# CPU.net
KiCad netlist of a schematic drawn in Altium Designer
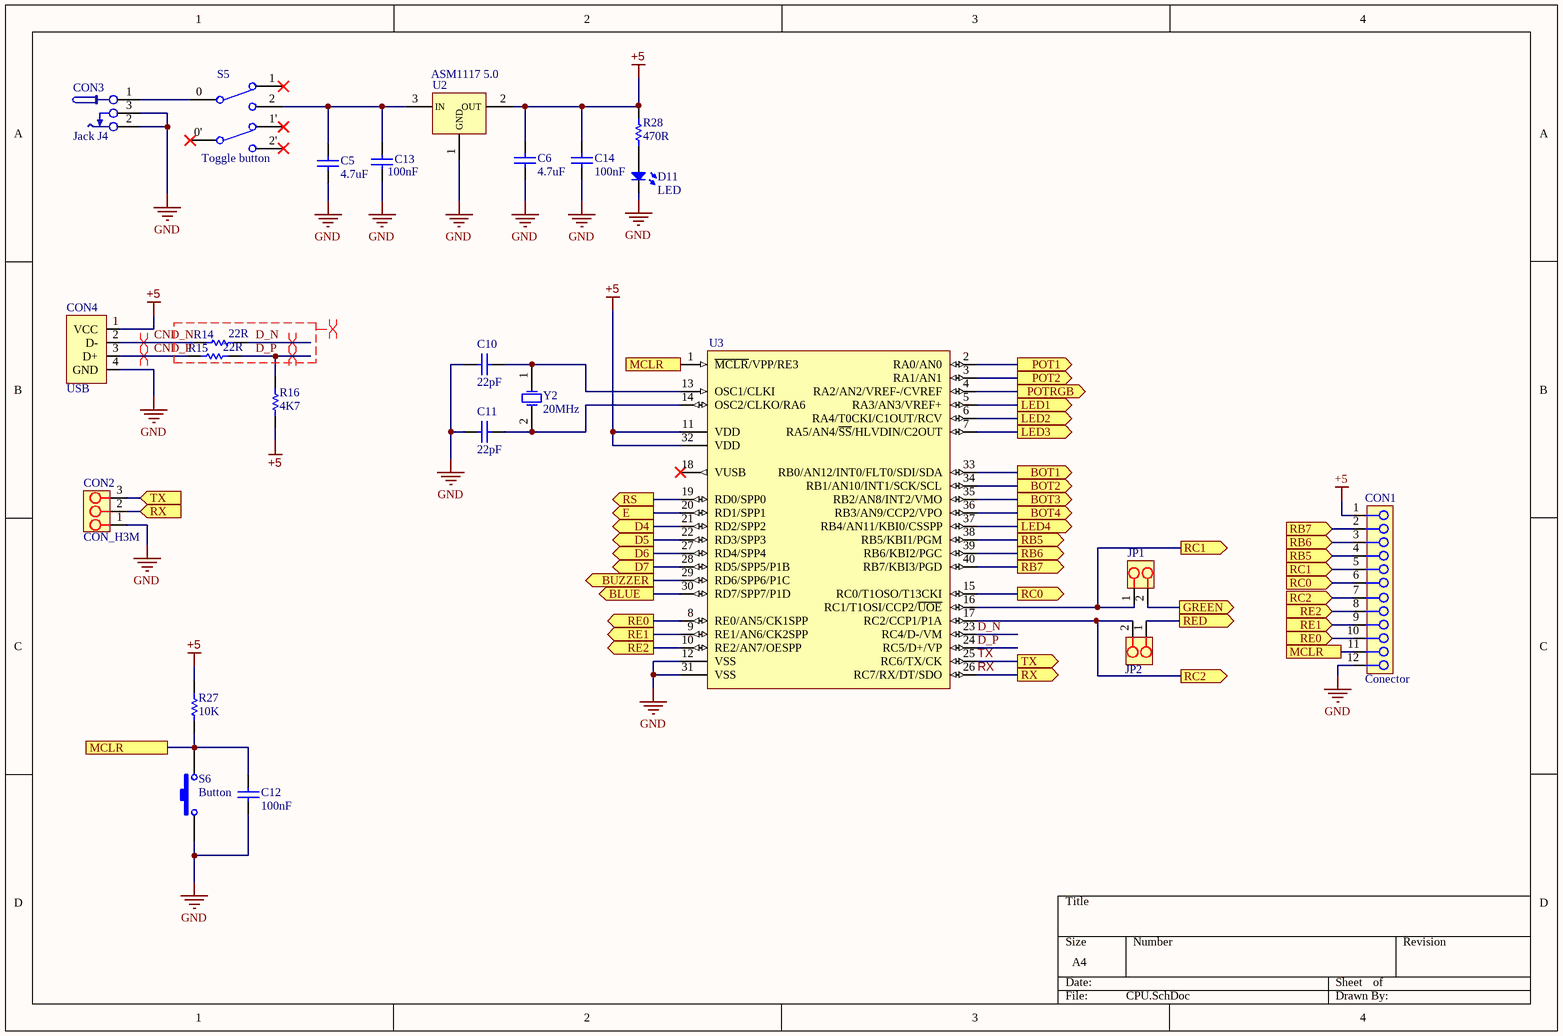
[diagram p0: CPU.SchDoc]

(export (version "E")
  (design (tool "Eeschema 10.0.6"))
  (components
    (comp (ref "C5")
      (value "4.7uF")
      (footprint "CAP_ELEC_1206")
      (description "Capacitor Cerâmico SMD X7R 50V - 1206")
      (libsource (lib "HEIMDALL-DEVPICKIT-V2.1") (part "SMD Eletrolitic Capacitor"))
    )
    (comp (ref "C6")
      (value "4.7uF")
      (footprint "CAP_ELEC_1206")
      (description "Capacitor Cerâmico SMD X7R 50V - 1206")
      (libsource (lib "HEIMDALL-DEVPICKIT-V2.1") (part "SMD Eletrolitic Capacitor"))
    )
    (comp (ref "C10")
      (value "22pF")
      (footprint "SMD Capacitor")
      (description "Multilayer Ceramic\r\nCapacitor 0805")
      (libsource (lib "Aken") (part "SMD Capacitor"))
    )
    (comp (ref "C11")
      (value "22pF")
      (footprint "SMD Capacitor")
      (description "Multilayer Ceramic\r\nCapacitor 0805")
      (libsource (lib "Aken") (part "SMD Capacitor"))
    )
    (comp (ref "C12")
      (value "100nF")
      (footprint "SMD Capacitor")
      (description "Multilayer Ceramic\r\nCapacitor 0805")
      (libsource (lib "Aken") (part "SMD Capacitor"))
    )
    (comp (ref "C13")
      (value "100nF")
      (footprint "SMD Capacitor")
      (description "Multilayer Ceramic\r\nCapacitor 0805")
      (libsource (lib "Aken") (part "SMD Capacitor"))
    )
    (comp (ref "C14")
      (value "100nF")
      (footprint "SMD Capacitor")
      (description "Multilayer Ceramic\r\nCapacitor 0805")
      (libsource (lib "Aken") (part "SMD Capacitor"))
    )
    (comp (ref "CON1") (value "Conector") (footprint "CON_6x2_M") (libsource (lib "Aken") (part "CON_6x2_M")))
    (comp (ref "CON2")
      (value "CON_H3M")
      (footprint "CON_3P_M")
      (description "Molex M 3T")
      (libsource (lib "Aken") (part "CON_H3M"))
    )
    (comp (ref "CON3")
      (value "Jack J4")
      (footprint "J4")
      (description "Conector DC Power Jack J4 2.5mm")
      (fields (field (name "MANUFACTURER") "CUI") (field (name "MANUFACTURER PART NUMBER") "PJ-102BH"))
      (libsource (lib "Adono_Library2") (part "CON-J4"))
    )
    (comp (ref "CON4")
      (value "USB")
      (footprint "USB_SMD")
      (description "Porta USB \r\ntipo B femea")
      (libsource (lib "HEIMDALL-DEVPICKIT-V2.1") (part "Porta_USB_B"))
    )
    (comp (ref "D11")
      (value "LED")
      (footprint "LED_GREEN")
      (description "Light Emissor Diode - 5mm")
      (fields
        (field (name "MANUFACTURER") "Kingbright")
        (field (name "MANUFACTURER PART NUMBER") "WP7113LGD")
      )
      (libsource (lib "Adono_Library2") (part "LED-GREEN"))
    )
    (comp (ref "JP1")
      (value "CON_H2M")
      (footprint "Header2-M")
      (description "Molex M 2T")
      (fields (field (name "MANUFACTURER") "Harwin") (field (name "MANUFACTURER PART NUMBER") "M20-9990246"))
      (libsource (lib "") (part "CON_H2M_1"))
    )
    (comp (ref "JP2")
      (value "CON_H2M")
      (footprint "Header2-M")
      (description "Molex M 2T")
      (fields (field (name "MANUFACTURER") "Harwin") (field (name "MANUFACTURER PART NUMBER") "M20-9990246"))
      (libsource (lib "Adono_Library") (part "CON_H2M"))
    )
    (comp (ref "R14")
      (value "22R")
      (footprint "SMD Resistor")
      (description "SMD Resistor  MCU 0805")
      (libsource (lib "HEIMDALL-DEVPICKIT-V2.1") (part "SMD Resistor"))
    )
    (comp (ref "R15")
      (value "22R")
      (footprint "SMD Resistor")
      (description "SMD Resistor  MCU 0805")
      (libsource (lib "HEIMDALL-DEVPICKIT-V2.1") (part "SMD Resistor"))
    )
    (comp (ref "R16")
      (value "4K7")
      (footprint "SMD Resistor")
      (description "SMD Resistor  MCU 0805")
      (libsource (lib "HEIMDALL-DEVPICKIT-V2.1") (part "SMD Resistor"))
    )
    (comp (ref "R27")
      (value "10K")
      (footprint "SMD Resistor")
      (description "SMD Resistor  MCU 0805")
      (libsource (lib "Aken") (part "SMD Resistor"))
    )
    (comp (ref "R28")
      (value "470R")
      (footprint "SMD Resistor")
      (description "SMD Resistor  MCU 0805")
      (libsource (lib "Aken") (part "SMD Resistor"))
    )
    (comp (ref "S5")
      (value "Toggle button")
      (footprint "Toggle button")
      (libsource (lib "Aken") (part "Toggle button"))
    )
    (comp (ref "S6")
      (value "Button")
      (footprint "BUTTON")
      (description "Tactil Switch")
      (fields
        (field (name "MANUFACTURER") "Panasonic")
        (field (name "MANUFACTURER PART NUMBER") "EVQ-PAC07K")
      )
      (libsource (lib "Adono_Library2") (part "Button"))
    )
    (comp (ref "U2")
      (value "ASM1117 5.0")
      (footprint "ASM1117 5.0")
      (description "LOW DROPOUT VOLTAGE REGULATOR")
      (libsource (lib "Aken") (part "ASM1117 5.0"))
    )
    (comp (ref "U3")
      (value "PIC18F4550")
      (footprint "DIP40")
      (fields
        (field (name "MANUFACTURER") "Microchip")
        (field (name "MANUFACTURER PART NUMBER") "PIC18F4550-I/P")
      )
      (libsource (lib "Adono_Library2") (part "PIC18F4550"))
    )
    (comp (ref "Y2")
      (value "20MHz")
      (footprint "CRYSTAL")
      (description "Quartz Crystal")
      (fields
        (field (name "MANUFACTURER") "ECS International")
        (field (name "MANUFACTURER PART NUMBER") "ECS-200-18-4XEN")
      )
      (libsource (lib "Adono_Library") (part "Crystal_Oscillator"))
    )
  )
  (nets
    (net (code "1") (name "+5") (class "Default")
      (node (ref "C14") (pin "2") (pinfunction "2_2") (pintype "passive"))
      (node (ref "C6") (pin "2") (pinfunction "2_2") (pintype "passive"))
      (node (ref "CON1") (pin "1") (pinfunction "1_1") (pintype "passive"))
      (node (ref "CON4") (pin "1") (pinfunction "VCC_1") (pintype "passive"))
      (node (ref "R16") (pin "1") (pinfunction "1_1") (pintype "passive"))
      (node (ref "R27") (pin "2") (pinfunction "2_2") (pintype "passive"))
      (node (ref "R28") (pin "2") (pinfunction "2_2") (pintype "passive"))
      (node (ref "U2") (pin "2") (pinfunction "OUT_2") (pintype "passive"))
      (node (ref "U3") (pin "11") (pinfunction "VDD_11") (pintype "power_in"))
      (node (ref "U3") (pin "32") (pinfunction "VDD_32") (pintype "power_in"))
    )
    (net (code "2") (name "/BLUE") (class "Default")
      (node (ref "U3") (pin "30") (pinfunction "RD7/SPP7/P1D_30") (pintype "bidirectional"))
    )
    (net (code "3") (name "/BOT1") (class "Default")
      (node (ref "U3") (pin "33") (pinfunction "RB0/AN12/INT0/FLT0/SDI/SDA_33") (pintype "bidirectional"))
    )
    (net (code "4") (name "/BOT2") (class "Default")
      (node (ref "U3") (pin "34") (pinfunction "RB1/AN10/INT1/SCK/SCL_34") (pintype "bidirectional"))
    )
    (net (code "5") (name "/BOT3") (class "Default")
      (node (ref "U3") (pin "35") (pinfunction "RB2/AN8/INT2/VMO_35") (pintype "bidirectional"))
    )
    (net (code "6") (name "/BOT4") (class "Default")
      (node (ref "U3") (pin "36") (pinfunction "RB3/AN9/CCP2/VPO_36") (pintype "bidirectional"))
    )
    (net (code "7") (name "/BUZZER") (class "Default")
      (node (ref "U3") (pin "29") (pinfunction "RD6/SPP6/P1C_29") (pintype "bidirectional"))
    )
    (net (code "8") (name "/CND_N") (class "Default")
      (node (ref "CON4") (pin "2") (pinfunction "D-_2") (pintype "passive"))
      (node (ref "R14") (pin "1") (pinfunction "1_1") (pintype "passive"))
    )
    (net (code "9") (name "/CND_P") (class "Default")
      (node (ref "CON4") (pin "3") (pinfunction "D+_3") (pintype "passive"))
      (node (ref "R15") (pin "1") (pinfunction "1_1") (pintype "passive"))
    )
    (net (code "10") (name "/D4") (class "Default")
      (node (ref "U3") (pin "21") (pinfunction "RD2/SPP2_21") (pintype "bidirectional"))
    )
    (net (code "11") (name "/D5") (class "Default")
      (node (ref "U3") (pin "22") (pinfunction "RD3/SPP3_22") (pintype "bidirectional"))
    )
    (net (code "12") (name "/D6") (class "Default")
      (node (ref "U3") (pin "27") (pinfunction "RD4/SPP4_27") (pintype "bidirectional"))
    )
    (net (code "13") (name "/D7") (class "Default")
      (node (ref "U3") (pin "28") (pinfunction "RD5/SPP5/P1B_28") (pintype "bidirectional"))
    )
    (net (code "14") (name "/D_N") (class "Default")
      (node (ref "R14") (pin "2") (pinfunction "2_2") (pintype "passive"))
      (node (ref "U3") (pin "23") (pinfunction "RC4/D-/VM_23") (pintype "bidirectional"))
    )
    (net (code "15") (name "/D_P") (class "Default")
      (node (ref "R15") (pin "2") (pinfunction "2_2") (pintype "passive"))
      (node (ref "R16") (pin "2") (pinfunction "2_2") (pintype "passive"))
      (node (ref "U3") (pin "24") (pinfunction "RC5/D+/VP_24") (pintype "bidirectional"))
    )
    (net (code "16") (name "/E") (class "Default")
      (node (ref "U3") (pin "20") (pinfunction "RD1/SPP1_20") (pintype "bidirectional"))
    )
    (net (code "17") (name "/GREEN") (class "Default")
      (node (ref "JP1") (pin "2") (pinfunction "2_2") (pintype "passive"))
    )
    (net (code "18") (name "/LED1") (class "Default")
      (node (ref "U3") (pin "5") (pinfunction "RA3/AN3/VREF+_5") (pintype "bidirectional"))
    )
    (net (code "19") (name "/LED2") (class "Default")
      (node (ref "U3") (pin "6") (pinfunction "RA4/T0CKI/C1OUT/RCV_6") (pintype "bidirectional"))
    )
    (net (code "20") (name "/LED3") (class "Default")
      (node (ref "U3") (pin "7") (pinfunction "RA5/AN4/~{SS}/HLVDIN/C2OUT_7") (pintype "bidirectional"))
    )
    (net (code "21") (name "/LED4") (class "Default")
      (node (ref "U3") (pin "37") (pinfunction "RB4/AN11/KBI0/CSSPP_37") (pintype "bidirectional"))
    )
    (net (code "22") (name "/MCLR") (class "Default")
      (node (ref "C12") (pin "2") (pinfunction "2_2") (pintype "passive"))
      (node (ref "CON1") (pin "11") (pinfunction "11_11") (pintype "passive"))
      (node (ref "R27") (pin "1") (pinfunction "1_1") (pintype "passive"))
      (node (ref "S6") (pin "2") (pinfunction "2_2") (pintype "passive"))
      (node (ref "U3") (pin "1") (pinfunction "~{MCLR}/VPP/RE3_1") (pintype "input"))
    )
    (net (code "23") (name "/POT1") (class "Default")
      (node (ref "U3") (pin "2") (pinfunction "RA0/AN0_2") (pintype "bidirectional"))
    )
    (net (code "24") (name "/POT2") (class "Default")
      (node (ref "U3") (pin "3") (pinfunction "RA1/AN1_3") (pintype "bidirectional"))
    )
    (net (code "25") (name "/POTRGB") (class "Default")
      (node (ref "U3") (pin "4") (pinfunction "RA2/AN2/VREF-/CVREF_4") (pintype "bidirectional"))
    )
    (net (code "26") (name "/RB5") (class "Default")
      (node (ref "CON1") (pin "4") (pinfunction "4_4") (pintype "passive"))
      (node (ref "U3") (pin "38") (pinfunction "RB5/KBI1/PGM_38") (pintype "bidirectional"))
    )
    (net (code "27") (name "/RB6") (class "Default")
      (node (ref "CON1") (pin "3") (pinfunction "3_3") (pintype "passive"))
      (node (ref "U3") (pin "39") (pinfunction "RB6/KBI2/PGC_39") (pintype "bidirectional"))
    )
    (net (code "28") (name "/RB7") (class "Default")
      (node (ref "CON1") (pin "2") (pinfunction "2_2") (pintype "passive"))
      (node (ref "U3") (pin "40") (pinfunction "RB7/KBI3/PGD_40") (pintype "bidirectional"))
    )
    (net (code "29") (name "/RC0") (class "Default")
      (node (ref "CON1") (pin "6") (pinfunction "6_6") (pintype "passive"))
      (node (ref "U3") (pin "15") (pinfunction "RC0/T1OSO/T13CKI_15") (pintype "bidirectional"))
    )
    (net (code "30") (name "/RC1") (class "Default")
      (node (ref "CON1") (pin "5") (pinfunction "5_5") (pintype "passive"))
      (node (ref "JP1") (pin "1") (pinfunction "1_1") (pintype "passive"))
      (node (ref "U3") (pin "16") (pinfunction "RC1/T1OSI/CCP2/~{UOE}_16") (pintype "bidirectional"))
    )
    (net (code "31") (name "/RC2") (class "Default")
      (node (ref "CON1") (pin "7") (pinfunction "7_7") (pintype "passive"))
      (node (ref "JP2") (pin "2") (pinfunction "2_2") (pintype "passive"))
      (node (ref "U3") (pin "17") (pinfunction "RC2/CCP1/P1A_17") (pintype "bidirectional"))
    )
    (net (code "32") (name "/RE0") (class "Default")
      (node (ref "CON1") (pin "10") (pinfunction "10_10") (pintype "passive"))
      (node (ref "U3") (pin "8") (pinfunction "RE0/AN5/CK1SPP_8") (pintype "bidirectional"))
    )
    (net (code "33") (name "/RE1") (class "Default")
      (node (ref "CON1") (pin "9") (pinfunction "9_9") (pintype "passive"))
      (node (ref "U3") (pin "9") (pinfunction "RE1/AN6/CK2SPP_9") (pintype "bidirectional"))
    )
    (net (code "34") (name "/RE2") (class "Default")
      (node (ref "CON1") (pin "8") (pinfunction "8_8") (pintype "passive"))
      (node (ref "U3") (pin "10") (pinfunction "RE2/AN7/OESPP_10") (pintype "bidirectional"))
    )
    (net (code "35") (name "/RED") (class "Default")
      (node (ref "JP2") (pin "1") (pinfunction "1_1") (pintype "passive"))
    )
    (net (code "36") (name "/RS") (class "Default")
      (node (ref "U3") (pin "19") (pinfunction "RD0/SPP0_19") (pintype "bidirectional"))
    )
    (net (code "37") (name "/RX") (class "Default")
      (node (ref "CON2") (pin "2") (pinfunction "2_2") (pintype "passive"))
      (node (ref "U3") (pin "26") (pinfunction "RC7/RX/DT/SDO_26") (pintype "bidirectional"))
    )
    (net (code "38") (name "/TX") (class "Default")
      (node (ref "CON2") (pin "3") (pinfunction "3_3") (pintype "passive"))
      (node (ref "U3") (pin "25") (pinfunction "RC6/TX/CK_25") (pintype "bidirectional"))
    )
    (net (code "39") (name "GND") (class "Default")
      (node (ref "C10") (pin "1") (pinfunction "1_1") (pintype "passive"))
      (node (ref "C11") (pin "1") (pinfunction "1_1") (pintype "passive"))
      (node (ref "C12") (pin "1") (pinfunction "1_1") (pintype "passive"))
      (node (ref "C13") (pin "1") (pinfunction "1_1") (pintype "passive"))
      (node (ref "C14") (pin "1") (pinfunction "1_1") (pintype "passive"))
      (node (ref "C5") (pin "1") (pinfunction "1_1") (pintype "passive"))
      (node (ref "C6") (pin "1") (pinfunction "1_1") (pintype "passive"))
      (node (ref "CON1") (pin "12") (pinfunction "12_12") (pintype "passive"))
      (node (ref "CON2") (pin "1") (pinfunction "1_1") (pintype "passive"))
      (node (ref "CON3") (pin "2") (pinfunction "2_2") (pintype "passive"))
      (node (ref "CON3") (pin "3") (pinfunction "3_3") (pintype "passive"))
      (node (ref "CON4") (pin "4") (pinfunction "GND_4") (pintype "passive"))
      (node (ref "D11") (pin "K") (pinfunction "K_K") (pintype "passive"))
      (node (ref "S6") (pin "1") (pinfunction "1_1") (pintype "passive"))
      (node (ref "U2") (pin "1") (pinfunction "GND_1") (pintype "passive"))
      (node (ref "U3") (pin "12") (pinfunction "VSS_12") (pintype "power_in"))
      (node (ref "U3") (pin "31") (pinfunction "VSS_31") (pintype "power_in"))
    )
    (net (code "40") (name "Net-(CON3-Pad1)") (class "Default")
      (node (ref "CON3") (pin "1") (pinfunction "1_1") (pintype "passive"))
      (node (ref "S5") (pin "0") (pinfunction "0_0") (pintype "passive"))
    )
    (net (code "41") (name "Net-(D11-PadA)") (class "Default")
      (node (ref "D11") (pin "A") (pinfunction "A_A") (pintype "passive"))
      (node (ref "R28") (pin "1") (pinfunction "1_1") (pintype "passive"))
    )
    (net (code "42") (name "Net-(U2-IN)") (class "Default")
      (node (ref "C13") (pin "2") (pinfunction "2_2") (pintype "passive"))
      (node (ref "C5") (pin "2") (pinfunction "2_2") (pintype "passive"))
      (node (ref "S5") (pin "2") (pinfunction "2_2") (pintype "passive"))
      (node (ref "U2") (pin "3") (pinfunction "IN_3") (pintype "passive"))
    )
    (net (code "43") (name "Net-(U3-OSC1{slash}CLKI)") (class "Default")
      (node (ref "C10") (pin "2") (pinfunction "2_2") (pintype "passive"))
      (node (ref "U3") (pin "13") (pinfunction "OSC1/CLKI_13") (pintype "input"))
      (node (ref "Y2") (pin "1") (pinfunction "OSC1_1") (pintype "passive"))
    )
    (net (code "44") (name "Net-(U3-OSC2{slash}CLKO{slash}RA6)") (class "Default")
      (node (ref "C11") (pin "2") (pinfunction "2_2") (pintype "passive"))
      (node (ref "U3") (pin "14") (pinfunction "OSC2/CLKO/RA6_14") (pintype "bidirectional"))
      (node (ref "Y2") (pin "2") (pinfunction "OSC2_2") (pintype "passive"))
    )
    (net (code "45") (name "unconnected-(S5-Pad0')") (class "Default")
      (node (ref "S5") (pin "0'") (pinfunction "0'_0'") (pintype "passive"))
    )
    (net (code "46") (name "unconnected-(S5-Pad1')") (class "Default")
      (node (ref "S5") (pin "1'") (pinfunction "1'_1'") (pintype "passive+no_connect"))
    )
    (net (code "47") (name "unconnected-(S5-Pad1)") (class "Default")
      (node (ref "S5") (pin "1") (pinfunction "1_1") (pintype "passive+no_connect"))
    )
    (net (code "48") (name "unconnected-(S5-Pad2')") (class "Default")
      (node (ref "S5") (pin "2'") (pinfunction "2'_2'") (pintype "passive+no_connect"))
    )
    (net (code "49") (name "unconnected-(U3-VUSB-Pad18)") (class "Default")
      (node (ref "U3") (pin "18") (pinfunction "VUSB_18") (pintype "output+no_connect"))
    )
  )
)
